# ESP32-C6-WROOM_Breakout.net
KiCad netlist of a schematic drawn in EAGLE
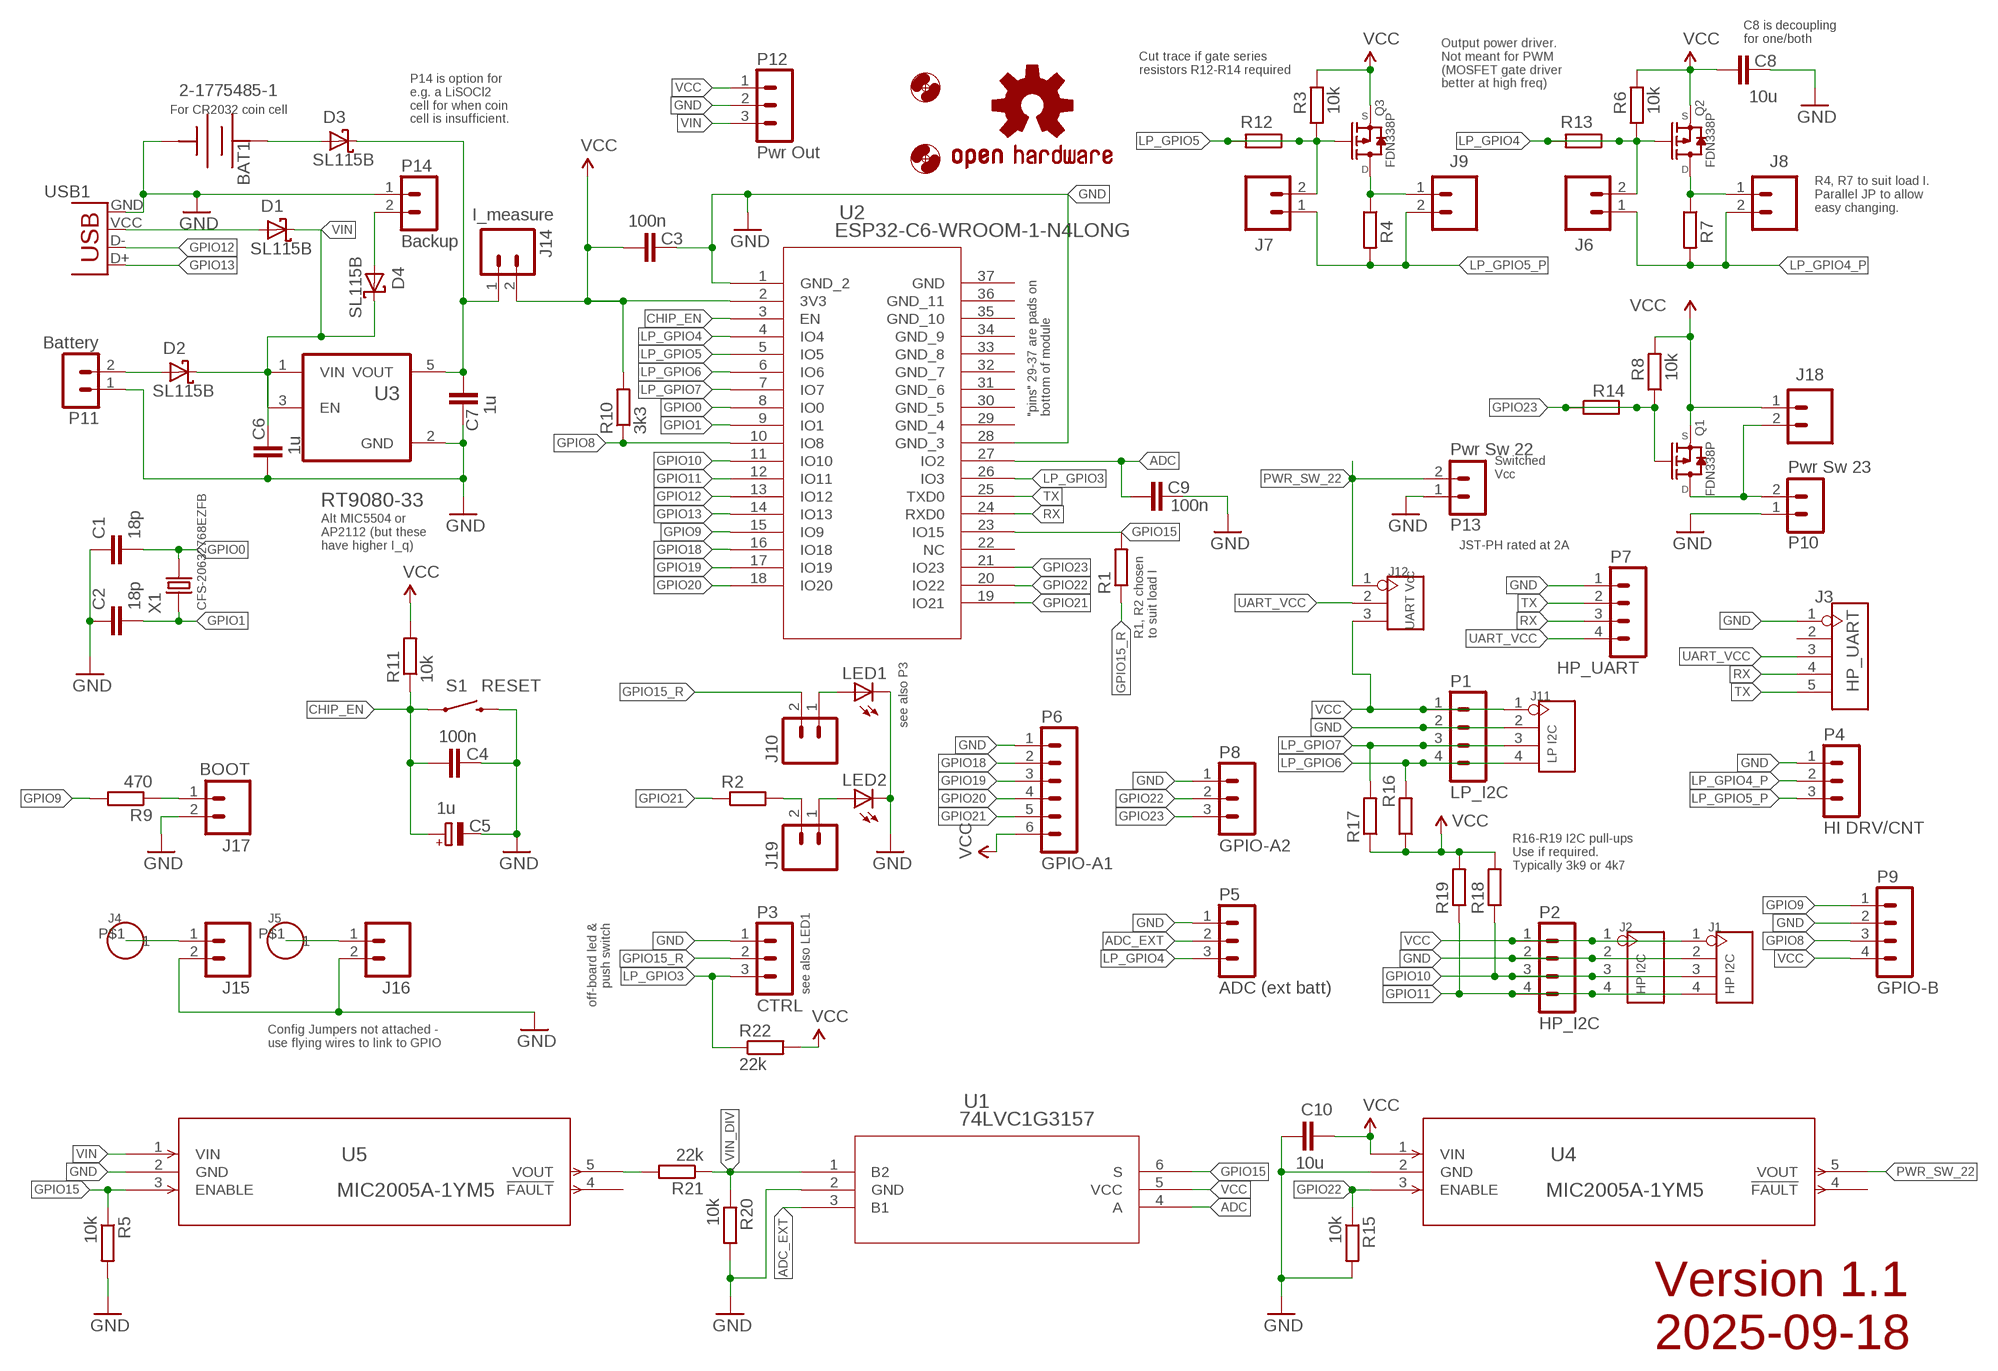
[diagram p0: schematic, sheet 1]

(export (version "E")
  (design (tool "Eeschema 10.0.6"))
  (components
    (comp (ref "BAT1")
      (value "2-1775485-1")
      (footprint "eagle-import:COIN_2-1775485-1_TEC")
      (libsource (lib "eagle-import") (part "COIN-CELL"))
    )
    (comp (ref "C1")
      (value "18p")
      (footprint "eagle-import:1206")
      (libsource (lib "eagle-import") (part "C-EU1206"))
    )
    (comp (ref "C2")
      (value "18p")
      (footprint "eagle-import:1206")
      (libsource (lib "eagle-import") (part "C-EU1206"))
    )
    (comp (ref "C3")
      (value "100n")
      (footprint "eagle-import:1206")
      (libsource (lib "eagle-import") (part "C-EU1206"))
    )
    (comp (ref "C4")
      (value "100n")
      (footprint "eagle-import:1206")
      (libsource (lib "eagle-import") (part "C-EU1206"))
    )
    (comp (ref "C5")
      (value "1u")
      (footprint "eagle-import:E2,5-5")
      (libsource (lib "eagle-import") (part "CPOL-EUE2.5-510UF"))
    )
    (comp (ref "C6")
      (value "1u")
      (footprint "eagle-import:1206")
      (libsource (lib "eagle-import") (part "C-EU1206"))
    )
    (comp (ref "C7")
      (value "1u")
      (footprint "eagle-import:1206")
      (libsource (lib "eagle-import") (part "C-EU1206"))
    )
    (comp (ref "C8")
      (value "10u")
      (footprint "eagle-import:1206")
      (libsource (lib "eagle-import") (part "C-EU1206"))
    )
    (comp (ref "C9")
      (value "100n")
      (footprint "eagle-import:1206")
      (libsource (lib "eagle-import") (part "C-EU1206"))
    )
    (comp (ref "C10")
      (value "10u")
      (footprint "eagle-import:1206")
      (libsource (lib "eagle-import") (part "C-EU1206"))
    )
    (comp (ref "D1")
      (value "SL115B")
      (footprint "eagle-import:DO-214AA")
      (libsource (lib "eagle-import") (part "DIODE-SCHOTTKY"))
    )
    (comp (ref "D2")
      (value "SL115B")
      (footprint "eagle-import:DO-214AA")
      (libsource (lib "eagle-import") (part "DIODE-SCHOTTKY"))
    )
    (comp (ref "D3")
      (value "SL115B")
      (footprint "eagle-import:DO-214AA")
      (libsource (lib "eagle-import") (part "DIODE-SCHOTTKY"))
    )
    (comp (ref "D4")
      (value "SL115B")
      (footprint "eagle-import:DO-214AA")
      (libsource (lib "eagle-import") (part "DIODE-SCHOTTKY"))
    )
    (comp (ref "H1")
      (value "MOUNT-HOLE2.8")
      (footprint "eagle-import:2,8")
      (libsource (lib "eagle-import") (part "MOUNT-HOLE2.8"))
    )
    (comp (ref "H2")
      (value "MOUNT-HOLE2.8")
      (footprint "eagle-import:2,8")
      (libsource (lib "eagle-import") (part "MOUNT-HOLE2.8"))
    )
    (comp (ref "J1")
      (value "HP I2C")
      (footprint "eagle-import:4P-2.54-80_40MIL")
      (libsource (lib "eagle-import") (part "HEADER-4P-80/40MIL"))
    )
    (comp (ref "J2")
      (value "HP I2C")
      (footprint "eagle-import:4P-2.54-80_40MIL")
      (libsource (lib "eagle-import") (part "HEADER-4P-80/40MIL"))
    )
    (comp (ref "J3")
      (value "HP_UART")
      (footprint "eagle-import:5P-2.54")
      (libsource (lib "eagle-import") (part "HEADER-5P-2.54"))
    )
    (comp (ref "J4")
      (value "HEADER-1P-35")
      (footprint "eagle-import:1P-65_35MIL")
      (libsource (lib "eagle-import") (part "HEADER-1P-35"))
    )
    (comp (ref "J5")
      (value "HEADER-1P-35")
      (footprint "eagle-import:1P-65_35MIL")
      (libsource (lib "eagle-import") (part "HEADER-1P-35"))
    )
    (comp (ref "J6")
      (value "HEADER-1X2PPTH")
      (footprint "eagle-import:1X02")
      (libsource (lib "eagle-import") (part "HEADER-1X2PPTH"))
    )
    (comp (ref "J7")
      (value "HEADER-1X2PPTH")
      (footprint "eagle-import:1X02")
      (libsource (lib "eagle-import") (part "HEADER-1X2PPTH"))
    )
    (comp (ref "J8")
      (value "HEADER-1X2PPTH")
      (footprint "eagle-import:1X02")
      (libsource (lib "eagle-import") (part "HEADER-1X2PPTH"))
    )
    (comp (ref "J9")
      (value "HEADER-1X2PPTH")
      (footprint "eagle-import:1X02")
      (libsource (lib "eagle-import") (part "HEADER-1X2PPTH"))
    )
    (comp (ref "J10")
      (value "HEADER-1X2PPTH")
      (footprint "eagle-import:1X02")
      (libsource (lib "eagle-import") (part "HEADER-1X2PPTH"))
    )
    (comp (ref "J11")
      (value "LP I2C")
      (footprint "eagle-import:4P-2.54-80_40MIL")
      (libsource (lib "eagle-import") (part "HEADER-4P-80/40MIL"))
    )
    (comp (ref "J12")
      (value "UART Vcc")
      (footprint "eagle-import:3P-2.54")
      (libsource (lib "eagle-import") (part "HEADER-3P-2.54"))
    )
    (comp (ref "J14")
      (value "I_measure")
      (footprint "eagle-import:1X02")
      (libsource (lib "eagle-import") (part "HEADER-1X2PPTH"))
    )
    (comp (ref "J15")
      (value "HEADER-1X2PPTH")
      (footprint "eagle-import:1X02")
      (libsource (lib "eagle-import") (part "HEADER-1X2PPTH"))
    )
    (comp (ref "J16")
      (value "HEADER-1X2PPTH")
      (footprint "eagle-import:1X02")
      (libsource (lib "eagle-import") (part "HEADER-1X2PPTH"))
    )
    (comp (ref "J17")
      (value "BOOT")
      (footprint "eagle-import:1X02")
      (libsource (lib "eagle-import") (part "HEADER-1X2PPTH"))
    )
    (comp (ref "J18")
      (value "HEADER-1X2PPTH")
      (footprint "eagle-import:1X02")
      (libsource (lib "eagle-import") (part "HEADER-1X2PPTH"))
    )
    (comp (ref "J19")
      (value "HEADER-1X2PPTH")
      (footprint "eagle-import:1X02")
      (libsource (lib "eagle-import") (part "HEADER-1X2PPTH"))
    )
    (comp (ref "LED1")
      (value "LED1206")
      (footprint "eagle-import:LED-1206")
      (libsource (lib "eagle-import") (part "LED1206"))
    )
    (comp (ref "LED2")
      (value "LED1206")
      (footprint "eagle-import:LED-1206")
      (libsource (lib "eagle-import") (part "LED1206"))
    )
    (comp (ref "LOGO1")
      (value "OSHW-LOGOL")
      (footprint "eagle-import:OSHW-LOGO-L")
      (libsource (lib "eagle-import") (part "OSHW-LOGOL"))
    )
    (comp (ref "P1")
      (value "LP_I2C")
      (footprint "eagle-import:B4B-EH-A")
      (libsource (lib "eagle-import") (part "B4B-EH-A"))
    )
    (comp (ref "P2")
      (value "HP_I2C")
      (footprint "eagle-import:B4B-EH-A")
      (libsource (lib "eagle-import") (part "B4B-EH-A"))
    )
    (comp (ref "P3")
      (value "CTRL")
      (footprint "eagle-import:B3B-EH-A")
      (libsource (lib "eagle-import") (part "B3B-EH-A"))
    )
    (comp (ref "P4")
      (value "HI DRV/CNT")
      (footprint "eagle-import:B3B-EH-A")
      (libsource (lib "eagle-import") (part "B3B-EH-A"))
    )
    (comp (ref "P5")
      (value "ADC (ext batt)")
      (footprint "eagle-import:B3B-EH-A")
      (libsource (lib "eagle-import") (part "B3B-EH-A"))
    )
    (comp (ref "P6")
      (value "GPIO-A1")
      (footprint "eagle-import:B6B-EH-A")
      (libsource (lib "eagle-import") (part "B6B-EH-A"))
    )
    (comp (ref "P7")
      (value "HP_UART")
      (footprint "eagle-import:B4B-EH-A")
      (libsource (lib "eagle-import") (part "B4B-EH-A"))
    )
    (comp (ref "P8")
      (value "GPIO-A2")
      (footprint "eagle-import:B3B-EH-A")
      (libsource (lib "eagle-import") (part "B3B-EH-A"))
    )
    (comp (ref "P9")
      (value "GPIO-B")
      (footprint "eagle-import:B4B-EH-A")
      (libsource (lib "eagle-import") (part "B4B-EH-A"))
    )
    (comp (ref "P10")
      (value "Pwr Sw 23")
      (footprint "eagle-import:B2B-PH-K")
      (libsource (lib "eagle-import") (part "B2B-PH-K"))
    )
    (comp (ref "P11")
      (value "Battery")
      (footprint "eagle-import:B2B-PH-K")
      (libsource (lib "eagle-import") (part "B2B-PH-K"))
    )
    (comp (ref "P12")
      (value "Pwr Out")
      (footprint "eagle-import:B3B-PH-K")
      (libsource (lib "eagle-import") (part "B3B-PH-K"))
    )
    (comp (ref "P13")
      (value "Pwr Sw 22")
      (footprint "eagle-import:B2B-PH-K")
      (libsource (lib "eagle-import") (part "B2B-PH-K"))
    )
    (comp (ref "P14")
      (value "Backup")
      (footprint "eagle-import:B2B-PH-K")
      (libsource (lib "eagle-import") (part "B2B-PH-K"))
    )
    (comp (ref "Q1")
      (value "FDN338P")
      (footprint "eagle-import:SOT23_LONG")
      (libsource (lib "eagle-import") (part "FDN338P_PMOSSOT23_LONG"))
    )
    (comp (ref "Q2")
      (value "FDN338P")
      (footprint "eagle-import:SOT23_LONG")
      (libsource (lib "eagle-import") (part "FDN338P_PMOSSOT23_LONG"))
    )
    (comp (ref "Q3")
      (value "FDN338P")
      (footprint "eagle-import:SOT23_LONG")
      (libsource (lib "eagle-import") (part "FDN338P_PMOSSOT23_LONG"))
    )
    (comp (ref "R1")
      (value "R-EU_")
      (footprint "eagle-import:1206")
      (libsource (lib "eagle-import") (part "R-EU_"))
    )
    (comp (ref "R2")
      (value "R-EU_")
      (footprint "eagle-import:1206")
      (libsource (lib "eagle-import") (part "R-EU_"))
    )
    (comp (ref "R3")
      (value "10k")
      (footprint "eagle-import:1206")
      (libsource (lib "eagle-import") (part "R-EU_"))
    )
    (comp (ref "R4")
      (value "R-EU_")
      (footprint "eagle-import:1206")
      (libsource (lib "eagle-import") (part "R-EU_"))
    )
    (comp (ref "R5")
      (value "10k")
      (footprint "eagle-import:1206")
      (libsource (lib "eagle-import") (part "R-EU_"))
    )
    (comp (ref "R6")
      (value "10k")
      (footprint "eagle-import:1206")
      (libsource (lib "eagle-import") (part "R-EU_"))
    )
    (comp (ref "R7")
      (value "R-EU_")
      (footprint "eagle-import:1206")
      (libsource (lib "eagle-import") (part "R-EU_"))
    )
    (comp (ref "R8")
      (value "10k")
      (footprint "eagle-import:1206")
      (libsource (lib "eagle-import") (part "R-EU_"))
    )
    (comp (ref "R9")
      (value "470")
      (footprint "eagle-import:1206")
      (libsource (lib "eagle-import") (part "R-EU_"))
    )
    (comp (ref "R10")
      (value "3k3")
      (footprint "eagle-import:1206")
      (libsource (lib "eagle-import") (part "R-EU_"))
    )
    (comp (ref "R11")
      (value "10k")
      (footprint "eagle-import:1206")
      (libsource (lib "eagle-import") (part "R-EU_"))
    )
    (comp (ref "R12")
      (value "R-EU_")
      (footprint "eagle-import:1206")
      (libsource (lib "eagle-import") (part "R-EU_"))
    )
    (comp (ref "R13")
      (value "R-EU_")
      (footprint "eagle-import:1206")
      (libsource (lib "eagle-import") (part "R-EU_"))
    )
    (comp (ref "R14")
      (value "R-EU_")
      (footprint "eagle-import:1206")
      (libsource (lib "eagle-import") (part "R-EU_"))
    )
    (comp (ref "R15")
      (value "10k")
      (footprint "eagle-import:1206")
      (libsource (lib "eagle-import") (part "R-EU_"))
    )
    (comp (ref "R16")
      (value "4k7")
      (footprint "eagle-import:1206")
      (libsource (lib "eagle-import") (part "R-EU_"))
    )
    (comp (ref "R17")
      (value "4k7")
      (footprint "eagle-import:1206")
      (libsource (lib "eagle-import") (part "R-EU_"))
    )
    (comp (ref "R18")
      (value "4k7")
      (footprint "eagle-import:1206")
      (libsource (lib "eagle-import") (part "R-EU_"))
    )
    (comp (ref "R19")
      (value "4k7")
      (footprint "eagle-import:1206")
      (libsource (lib "eagle-import") (part "R-EU_"))
    )
    (comp (ref "R20")
      (value "10k")
      (footprint "eagle-import:1206")
      (libsource (lib "eagle-import") (part "R-EU_"))
    )
    (comp (ref "R21")
      (value "22k")
      (footprint "eagle-import:1206")
      (libsource (lib "eagle-import") (part "R-EU_"))
    )
    (comp (ref "R22")
      (value "22k")
      (footprint "eagle-import:1206")
      (libsource (lib "eagle-import") (part "R-EU_"))
    )
    (comp (ref "S1")
      (value "RESET")
      (footprint "eagle-import:TACTILE-PTH")
      (libsource (lib "eagle-import") (part "SWITCH-MOMENTARY-2PTH"))
    )
    (comp (ref "U1")
      (value "74LVC1G3157")
      (footprint "eagle-import:DBV6")
      (fields
        (field (name "MANUFACTURER_PART_NUMBER") "SN74LVC1G3157DBVR")
        (field (name "COPYRIGHT") "Copyright (C) 2025 Ultra Librarian. All rights reserved.")
      )
      (libsource (lib "eagle-import") (part "SN74LVC1G3157DBVR"))
    )
    (comp (ref "U2")
      (value "ESP32-C6-WROOM-1-N4LONG")
      (footprint "eagle-import:MOD28_ESP32-C6-WROOM-1_LONG")
      (libsource (lib "eagle-import") (part "ESP32-C6-WROOM-1-N4LONG"))
    )
    (comp (ref "U3")
      (value "RT9080-33")
      (footprint "eagle-import:SOT95-LONGPADS")
      (libsource (lib "eagle-import") (part "AP2112K-3.3TRG1LONG_PADS"))
    )
    (comp (ref "U4")
      (value "MIC2005A-1YM5")
      (footprint "eagle-import:SOT-23-5_M5_MCH-M")
      (fields
        (field (name "MANUFACTURER_PART_NUMBER") "MIC2005A-1YM5-TR")
        (field (name "COPYRIGHT") "Copyright (C) 2025 Ultra Librarian. All rights reserved.")
      )
      (libsource (lib "eagle-import") (part "MIC2005A-1YM5-TRSOT-23-5_M5_MCH-M"))
    )
    (comp (ref "U5")
      (value "MIC2005A-1YM5")
      (footprint "eagle-import:SOT-23-5_M5_MCH-M")
      (fields
        (field (name "MANUFACTURER_PART_NUMBER") "MIC2005A-1YM5-TR")
        (field (name "COPYRIGHT") "Copyright (C) 2025 Ultra Librarian. All rights reserved.")
      )
      (libsource (lib "eagle-import") (part "MIC2005A-1YM5-TRSOT-23-5_M5_MCH-M"))
    )
    (comp (ref "USB1")
      (value "USB-FCI_SMD_LONG***")
      (footprint "eagle-import:FCI_USB_B_SMD_LONG")
      (libsource (lib "eagle-import") (part "USB-FCI_SMD_LONG"))
    )
    (comp (ref "X1")
      (value "CFS-20632768EZFB")
      (footprint "eagle-import:TC26H")
      (libsource (lib "eagle-import") (part "CRYSTAL-TC26H"))
    )
  )
  (nets
    (net (code "1") (name "ADC") (class "Default")
      (node (ref "C9") (pin "1") (pinfunction "1_1") (pintype "passive"))
      (node (ref "U1") (pin "4") (pinfunction "A_4") (pintype "input"))
      (node (ref "U2") (pin "27") (pinfunction "IO2_27") (pintype "bidirectional"))
    )
    (net (code "2") (name "ADC_EXT") (class "Default")
      (node (ref "P5") (pin "2") (pinfunction "2_2") (pintype "passive"))
      (node (ref "U1") (pin "3") (pinfunction "B1_3") (pintype "input"))
    )
    (net (code "3") (name "CHIP_EN") (class "Default")
      (node (ref "C4") (pin "2") (pinfunction "2_2") (pintype "passive"))
      (node (ref "C5") (pin "+") (pinfunction "+_+") (pintype "passive"))
      (node (ref "R11") (pin "1") (pinfunction "1_1") (pintype "passive"))
      (node (ref "S1") (pin "1") (pinfunction "1_1") (pintype "passive"))
      (node (ref "U2") (pin "3") (pinfunction "EN_3") (pintype "input"))
    )
    (net (code "4") (name "GND") (class "Default")
      (node (ref "BAT1") (pin "2") (pinfunction "NEG_2") (pintype "bidirectional"))
      (node (ref "C1") (pin "1") (pinfunction "1_1") (pintype "passive"))
      (node (ref "C10") (pin "1") (pinfunction "1_1") (pintype "passive"))
      (node (ref "C2") (pin "1") (pinfunction "1_1") (pintype "passive"))
      (node (ref "C3") (pin "2") (pinfunction "2_2") (pintype "passive"))
      (node (ref "C4") (pin "1") (pinfunction "1_1") (pintype "passive"))
      (node (ref "C5") (pin "-") (pinfunction "-_-") (pintype "passive"))
      (node (ref "C6") (pin "2") (pinfunction "2_2") (pintype "passive"))
      (node (ref "C7") (pin "2") (pinfunction "2_2") (pintype "passive"))
      (node (ref "C8") (pin "2") (pinfunction "2_2") (pintype "passive"))
      (node (ref "C9") (pin "2") (pinfunction "2_2") (pintype "passive"))
      (node (ref "J1") (pin "2") (pinfunction "P$2_2") (pintype "bidirectional"))
      (node (ref "J11") (pin "2") (pinfunction "P$2_2") (pintype "bidirectional"))
      (node (ref "J15") (pin "2") (pinfunction "2_2") (pintype "passive"))
      (node (ref "J16") (pin "2") (pinfunction "2_2") (pintype "passive"))
      (node (ref "J17") (pin "2") (pinfunction "2_2") (pintype "passive"))
      (node (ref "J2") (pin "2") (pinfunction "P$2_2") (pintype "bidirectional"))
      (node (ref "J3") (pin "1") (pinfunction "1_1") (pintype "bidirectional"))
      (node (ref "LED1") (pin "C") (pinfunction "C_C") (pintype "passive"))
      (node (ref "LED2") (pin "C") (pinfunction "C_C") (pintype "passive"))
      (node (ref "P1") (pin "2") (pinfunction "2_2") (pintype "passive"))
      (node (ref "P10") (pin "1") (pinfunction "1_1") (pintype "passive"))
      (node (ref "P11") (pin "1") (pinfunction "1_1") (pintype "passive"))
      (node (ref "P12") (pin "2") (pinfunction "2_2") (pintype "passive"))
      (node (ref "P13") (pin "1") (pinfunction "1_1") (pintype "passive"))
      (node (ref "P14") (pin "1") (pinfunction "1_1") (pintype "passive"))
      (node (ref "P2") (pin "2") (pinfunction "2_2") (pintype "passive"))
      (node (ref "P3") (pin "1") (pinfunction "1_1") (pintype "passive"))
      (node (ref "P4") (pin "1") (pinfunction "1_1") (pintype "passive"))
      (node (ref "P5") (pin "1") (pinfunction "1_1") (pintype "passive"))
      (node (ref "P6") (pin "1") (pinfunction "1_1") (pintype "passive"))
      (node (ref "P7") (pin "1") (pinfunction "1_1") (pintype "passive"))
      (node (ref "P8") (pin "1") (pinfunction "1_1") (pintype "passive"))
      (node (ref "P9") (pin "2") (pinfunction "2_2") (pintype "passive"))
      (node (ref "R15") (pin "2") (pinfunction "2_2") (pintype "passive"))
      (node (ref "R20") (pin "2") (pinfunction "2_2") (pintype "passive"))
      (node (ref "R5") (pin "2") (pinfunction "2_2") (pintype "passive"))
      (node (ref "S1") (pin "3") (pinfunction "2_3") (pintype "passive"))
      (node (ref "U1") (pin "2") (pinfunction "GND_2") (pintype "power_in"))
      (node (ref "U2") (pin "1") (pinfunction "GND_2_1") (pintype "passive"))
      (node (ref "U2") (pin "28") (pinfunction "GND_3_28") (pintype "passive"))
      (node (ref "U3") (pin "2") (pinfunction "GND_2") (pintype "power_in"))
      (node (ref "U4") (pin "2") (pinfunction "GND_2") (pintype "power_in"))
      (node (ref "U5") (pin "2") (pinfunction "GND_2") (pintype "power_in"))
      (node (ref "USB1") (pin "GND") (pinfunction "GND_GND") (pintype "bidirectional"))
    )
    (net (code "5") (name "GPIO0") (class "Default")
      (node (ref "C1") (pin "2") (pinfunction "2_2") (pintype "passive"))
      (node (ref "U2") (pin "8") (pinfunction "IO0_8") (pintype "bidirectional"))
      (node (ref "X1") (pin "2") (pinfunction "2_2") (pintype "passive"))
    )
    (net (code "6") (name "GPIO1") (class "Default")
      (node (ref "C2") (pin "2") (pinfunction "2_2") (pintype "passive"))
      (node (ref "U2") (pin "9") (pinfunction "IO1_9") (pintype "bidirectional"))
      (node (ref "X1") (pin "1") (pinfunction "1_1") (pintype "passive"))
    )
    (net (code "7") (name "GPIO8") (class "Default")
      (node (ref "P9") (pin "3") (pinfunction "3_3") (pintype "passive"))
      (node (ref "R10") (pin "1") (pinfunction "1_1") (pintype "passive"))
      (node (ref "U2") (pin "10") (pinfunction "IO8_10") (pintype "bidirectional"))
    )
    (net (code "8") (name "GPIO9") (class "Default")
      (node (ref "P9") (pin "1") (pinfunction "1_1") (pintype "passive"))
      (node (ref "R9") (pin "2") (pinfunction "2_2") (pintype "passive"))
      (node (ref "U2") (pin "15") (pinfunction "IO9_15") (pintype "bidirectional"))
    )
    (net (code "9") (name "GPIO10") (class "Default")
      (node (ref "J1") (pin "3") (pinfunction "P$3_3") (pintype "bidirectional"))
      (node (ref "J2") (pin "3") (pinfunction "P$3_3") (pintype "bidirectional"))
      (node (ref "P2") (pin "3") (pinfunction "3_3") (pintype "passive"))
      (node (ref "R18") (pin "1") (pinfunction "1_1") (pintype "passive"))
      (node (ref "U2") (pin "11") (pinfunction "IO10_11") (pintype "bidirectional"))
    )
    (net (code "10") (name "GPIO11") (class "Default")
      (node (ref "J1") (pin "4") (pinfunction "P$4_4") (pintype "bidirectional"))
      (node (ref "J2") (pin "4") (pinfunction "P$4_4") (pintype "bidirectional"))
      (node (ref "P2") (pin "4") (pinfunction "4_4") (pintype "passive"))
      (node (ref "R19") (pin "1") (pinfunction "1_1") (pintype "passive"))
      (node (ref "U2") (pin "12") (pinfunction "IO11_12") (pintype "bidirectional"))
    )
    (net (code "11") (name "GPIO12") (class "Default")
      (node (ref "U2") (pin "13") (pinfunction "IO12_13") (pintype "bidirectional"))
      (node (ref "USB1") (pin "D-") (pinfunction "D-_D-") (pintype "bidirectional"))
    )
    (net (code "12") (name "GPIO13") (class "Default")
      (node (ref "U2") (pin "14") (pinfunction "IO13_14") (pintype "bidirectional"))
      (node (ref "USB1") (pin "D+") (pinfunction "D+_D+") (pintype "bidirectional"))
    )
    (net (code "13") (name "GPIO15") (class "Default")
      (node (ref "R1") (pin "2") (pinfunction "2_2") (pintype "passive"))
      (node (ref "R5") (pin "1") (pinfunction "1_1") (pintype "passive"))
      (node (ref "U1") (pin "6") (pinfunction "S_6") (pintype "input"))
      (node (ref "U2") (pin "23") (pinfunction "IO15_23") (pintype "bidirectional"))
      (node (ref "U5") (pin "3") (pinfunction "ENABLE_3") (pintype "input"))
    )
    (net (code "14") (name "GPIO15_R") (class "Default")
      (node (ref "J10") (pin "2") (pinfunction "2_2") (pintype "passive"))
      (node (ref "P3") (pin "2") (pinfunction "2_2") (pintype "passive"))
      (node (ref "R1") (pin "1") (pinfunction "1_1") (pintype "passive"))
    )
    (net (code "15") (name "GPIO18") (class "Default")
      (node (ref "P6") (pin "2") (pinfunction "2_2") (pintype "passive"))
      (node (ref "U2") (pin "16") (pinfunction "IO18_16") (pintype "bidirectional"))
    )
    (net (code "16") (name "GPIO19") (class "Default")
      (node (ref "P6") (pin "3") (pinfunction "3_3") (pintype "passive"))
      (node (ref "U2") (pin "17") (pinfunction "IO19_17") (pintype "bidirectional"))
    )
    (net (code "17") (name "GPIO20") (class "Default")
      (node (ref "P6") (pin "4") (pinfunction "4_4") (pintype "passive"))
      (node (ref "U2") (pin "18") (pinfunction "IO20_18") (pintype "bidirectional"))
    )
    (net (code "18") (name "GPIO21") (class "Default")
      (node (ref "P6") (pin "5") (pinfunction "5_5") (pintype "passive"))
      (node (ref "R2") (pin "1") (pinfunction "1_1") (pintype "passive"))
      (node (ref "U2") (pin "19") (pinfunction "IO21_19") (pintype "bidirectional"))
    )
    (net (code "19") (name "GPIO22") (class "Default")
      (node (ref "P8") (pin "2") (pinfunction "2_2") (pintype "passive"))
      (node (ref "R15") (pin "1") (pinfunction "1_1") (pintype "passive"))
      (node (ref "U2") (pin "20") (pinfunction "IO22_20") (pintype "bidirectional"))
      (node (ref "U4") (pin "3") (pinfunction "ENABLE_3") (pintype "input"))
    )
    (net (code "20") (name "GPIO23") (class "Default")
      (node (ref "P8") (pin "3") (pinfunction "3_3") (pintype "passive"))
      (node (ref "Q1") (pin "1") (pinfunction "G_1") (pintype "passive"))
      (node (ref "R14") (pin "1") (pinfunction "1_1") (pintype "passive"))
      (node (ref "R14") (pin "2") (pinfunction "2_2") (pintype "passive"))
      (node (ref "R8") (pin "1") (pinfunction "1_1") (pintype "passive"))
      (node (ref "U2") (pin "21") (pinfunction "IO23_21") (pintype "bidirectional"))
    )
    (net (code "21") (name "LP_GPIO3") (class "Default")
      (node (ref "P3") (pin "3") (pinfunction "3_3") (pintype "passive"))
      (node (ref "R22") (pin "1") (pinfunction "1_1") (pintype "passive"))
      (node (ref "U2") (pin "26") (pinfunction "IO3_26") (pintype "bidirectional"))
    )
    (net (code "22") (name "LP_GPIO4") (class "Default")
      (node (ref "J6") (pin "2") (pinfunction "2_2") (pintype "passive"))
      (node (ref "P5") (pin "3") (pinfunction "3_3") (pintype "passive"))
      (node (ref "Q2") (pin "1") (pinfunction "G_1") (pintype "passive"))
      (node (ref "R13") (pin "1") (pinfunction "1_1") (pintype "passive"))
      (node (ref "R13") (pin "2") (pinfunction "2_2") (pintype "passive"))
      (node (ref "R6") (pin "1") (pinfunction "1_1") (pintype "passive"))
      (node (ref "U2") (pin "4") (pinfunction "IO4_4") (pintype "bidirectional"))
    )
    (net (code "23") (name "LP_GPIO4_P") (class "Default")
      (node (ref "J6") (pin "1") (pinfunction "1_1") (pintype "passive"))
      (node (ref "J8") (pin "2") (pinfunction "2_2") (pintype "passive"))
      (node (ref "P4") (pin "2") (pinfunction "2_2") (pintype "passive"))
      (node (ref "R7") (pin "2") (pinfunction "2_2") (pintype "passive"))
    )
    (net (code "24") (name "LP_GPIO5") (class "Default")
      (node (ref "J7") (pin "2") (pinfunction "2_2") (pintype "passive"))
      (node (ref "Q3") (pin "1") (pinfunction "G_1") (pintype "passive"))
      (node (ref "R12") (pin "1") (pinfunction "1_1") (pintype "passive"))
      (node (ref "R12") (pin "2") (pinfunction "2_2") (pintype "passive"))
      (node (ref "R3") (pin "1") (pinfunction "1_1") (pintype "passive"))
      (node (ref "U2") (pin "5") (pinfunction "IO5_5") (pintype "bidirectional"))
    )
    (net (code "25") (name "LP_GPIO5_P") (class "Default")
      (node (ref "J7") (pin "1") (pinfunction "1_1") (pintype "passive"))
      (node (ref "J9") (pin "2") (pinfunction "2_2") (pintype "passive"))
      (node (ref "P4") (pin "3") (pinfunction "3_3") (pintype "passive"))
      (node (ref "R4") (pin "2") (pinfunction "2_2") (pintype "passive"))
    )
    (net (code "26") (name "LP_GPIO6") (class "Default")
      (node (ref "J11") (pin "4") (pinfunction "P$4_4") (pintype "bidirectional"))
      (node (ref "P1") (pin "4") (pinfunction "4_4") (pintype "passive"))
      (node (ref "R16") (pin "2") (pinfunction "2_2") (pintype "passive"))
      (node (ref "U2") (pin "6") (pinfunction "IO6_6") (pintype "bidirectional"))
    )
    (net (code "27") (name "LP_GPIO7") (class "Default")
      (node (ref "J11") (pin "3") (pinfunction "P$3_3") (pintype "bidirectional"))
      (node (ref "P1") (pin "3") (pinfunction "3_3") (pintype "passive"))
      (node (ref "R17") (pin "2") (pinfunction "2_2") (pintype "passive"))
      (node (ref "U2") (pin "7") (pinfunction "IO7_7") (pintype "bidirectional"))
    )
    (net (code "28") (name "Net-(BAT1-POS-Pad1)") (class "Default")
      (node (ref "BAT1") (pin "1") (pinfunction "POS_1") (pintype "bidirectional"))
      (node (ref "BAT1") (pin "3") (pinfunction "POS_3") (pintype "bidirectional"))
      (node (ref "D3") (pin "A") (pinfunction "A_A") (pintype "passive"))
    )
    (net (code "29") (name "Net-(D2-PadA)") (class "Default")
      (node (ref "D2") (pin "A") (pinfunction "A_A") (pintype "passive"))
      (node (ref "P11") (pin "2") (pinfunction "2_2") (pintype "passive"))
    )
    (net (code "30") (name "Net-(D4-PadA)") (class "Default")
      (node (ref "D4") (pin "A") (pinfunction "A_A") (pintype "passive"))
      (node (ref "P14") (pin "2") (pinfunction "2_2") (pintype "passive"))
    )
    (net (code "31") (name "Net-(J4-1)") (class "Default")
      (node (ref "J15") (pin "1") (pinfunction "1_1") (pintype "passive"))
      (node (ref "J4") (pin "P$1") (pinfunction "1_P$1") (pintype "bidirectional"))
    )
    (net (code "32") (name "Net-(J5-1)") (class "Default")
      (node (ref "J16") (pin "1") (pinfunction "1_1") (pintype "passive"))
      (node (ref "J5") (pin "P$1") (pinfunction "1_P$1") (pintype "bidirectional"))
    )
    (net (code "33") (name "Net-(J10-Pad1)") (class "Default")
      (node (ref "J10") (pin "1") (pinfunction "1_1") (pintype "passive"))
      (node (ref "LED1") (pin "A") (pinfunction "A_A") (pintype "passive"))
    )
    (net (code "34") (name "Net-(J17-Pad1)") (class "Default")
      (node (ref "J17") (pin "1") (pinfunction "1_1") (pintype "passive"))
      (node (ref "R9") (pin "1") (pinfunction "1_1") (pintype "passive"))
    )
    (net (code "35") (name "Net-(J19-Pad1)") (class "Default")
      (node (ref "J19") (pin "1") (pinfunction "1_1") (pintype "passive"))
      (node (ref "LED2") (pin "A") (pinfunction "A_A") (pintype "passive"))
    )
    (net (code "36") (name "Net-(J19-Pad2)") (class "Default")
      (node (ref "J19") (pin "2") (pinfunction "2_2") (pintype "passive"))
      (node (ref "R2") (pin "2") (pinfunction "2_2") (pintype "passive"))
    )
    (net (code "37") (name "Net-(Q1-D)") (class "Default")
      (node (ref "J18") (pin "2") (pinfunction "2_2") (pintype "passive"))
      (node (ref "P10") (pin "2") (pinfunction "2_2") (pintype "passive"))
      (node (ref "Q1") (pin "3") (pinfunction "D_3") (pintype "passive"))
    )
    (net (code "38") (name "Net-(Q2-D)") (class "Default")
      (node (ref "J8") (pin "1") (pinfunction "1_1") (pintype "passive"))
      (node (ref "Q2") (pin "3") (pinfunction "D_3") (pintype "passive"))
      (node (ref "R7") (pin "1") (pinfunction "1_1") (pintype "passive"))
    )
    (net (code "39") (name "Net-(Q3-D)") (class "Default")
      (node (ref "J9") (pin "1") (pinfunction "1_1") (pintype "passive"))
      (node (ref "Q3") (pin "3") (pinfunction "D_3") (pintype "passive"))
      (node (ref "R4") (pin "1") (pinfunction "1_1") (pintype "passive"))
    )
    (net (code "40") (name "Net-(U3-VOUT)") (class "Default")
      (node (ref "C7") (pin "1") (pinfunction "1_1") (pintype "passive"))
      (node (ref "D3") (pin "C") (pinfunction "C_C") (pintype "passive"))
      (node (ref "J14") (pin "1") (pinfunction "1_1") (pintype "passive"))
      (node (ref "U3") (pin "5") (pinfunction "VOUT_5") (pintype "power_in"))
    )
    (net (code "41") (name "Net-(U5-VOUT)") (class "Default")
      (node (ref "R21") (pin "2") (pinfunction "2_2") (pintype "passive"))
      (node (ref "U5") (pin "5") (pinfunction "VOUT_5") (pintype "output"))
    )
    (net (code "42") (name "Net-(USB1-VBUS)") (class "Default")
      (node (ref "D1") (pin "A") (pinfunction "A_A") (pintype "passive"))
      (node (ref "USB1") (pin "VCC") (pinfunction "VBUS_VCC") (pintype "bidirectional"))
    )
    (net (code "43") (name "PWR_SW_22") (class "Default")
      (node (ref "J12") (pin "1") (pinfunction "P$1_1") (pintype "bidirectional"))
      (node (ref "P13") (pin "2") (pinfunction "2_2") (pintype "passive"))
      (node (ref "U4") (pin "5") (pinfunction "VOUT_5") (pintype "output"))
    )
    (net (code "44") (name "RX") (class "Default")
      (node (ref "J3") (pin "4") (pinfunction "4_4") (pintype "bidirectional"))
      (node (ref "P7") (pin "3") (pinfunction "3_3") (pintype "passive"))
      (node (ref "U2") (pin "24") (pinfunction "RXD0_24") (pintype "bidirectional"))
    )
    (net (code "45") (name "TX") (class "Default")
      (node (ref "J3") (pin "5") (pinfunction "5_5") (pintype "bidirectional"))
      (node (ref "P7") (pin "2") (pinfunction "2_2") (pintype "passive"))
      (node (ref "U2") (pin "25") (pinfunction "TXD0_25") (pintype "bidirectional"))
    )
    (net (code "46") (name "UART_VCC") (class "Default")
      (node (ref "J12") (pin "2") (pinfunction "P$2_2") (pintype "bidirectional"))
      (node (ref "J3") (pin "3") (pinfunction "3_3") (pintype "bidirectional"))
      (node (ref "P7") (pin "4") (pinfunction "4_4") (pintype "passive"))
    )
    (net (code "47") (name "VCC") (class "Default")
      (node (ref "C10") (pin "2") (pinfunction "2_2") (pintype "passive"))
      (node (ref "C3") (pin "1") (pinfunction "1_1") (pintype "passive"))
      (node (ref "C8") (pin "1") (pinfunction "1_1") (pintype "passive"))
      (node (ref "J1") (pin "1") (pinfunction "P$1_1") (pintype "bidirectional"))
      (node (ref "J11") (pin "1") (pinfunction "P$1_1") (pintype "bidirectional"))
      (node (ref "J12") (pin "3") (pinfunction "P$3_3") (pintype "bidirectional"))
      (node (ref "J14") (pin "2") (pinfunction "2_2") (pintype "passive"))
      (node (ref "J18") (pin "1") (pinfunction "1_1") (pintype "passive"))
      (node (ref "J2") (pin "1") (pinfunction "P$1_1") (pintype "bidirectional"))
      (node (ref "P1") (pin "1") (pinfunction "1_1") (pintype "passive"))
      (node (ref "P12") (pin "1") (pinfunction "1_1") (pintype "passive"))
      (node (ref "P2") (pin "1") (pinfunction "1_1") (pintype "passive"))
      (node (ref "P6") (pin "6") (pinfunction "6_6") (pintype "passive"))
      (node (ref "P9") (pin "4") (pinfunction "4_4") (pintype "passive"))
      (node (ref "Q1") (pin "2") (pinfunction "S_2") (pintype "passive"))
      (node (ref "Q2") (pin "2") (pinfunction "S_2") (pintype "passive"))
      (node (ref "Q3") (pin "2") (pinfunction "S_2") (pintype "passive"))
      (node (ref "R10") (pin "2") (pinfunction "2_2") (pintype "passive"))
      (node (ref "R11") (pin "2") (pinfunction "2_2") (pintype "passive"))
      (node (ref "R16") (pin "1") (pinfunction "1_1") (pintype "passive"))
      (node (ref "R17") (pin "1") (pinfunction "1_1") (pintype "passive"))
      (node (ref "R18") (pin "2") (pinfunction "2_2") (pintype "passive"))
      (node (ref "R19") (pin "2") (pinfunction "2_2") (pintype "passive"))
      (node (ref "R22") (pin "2") (pinfunction "2_2") (pintype "passive"))
      (node (ref "R3") (pin "2") (pinfunction "2_2") (pintype "passive"))
      (node (ref "R6") (pin "2") (pinfunction "2_2") (pintype "passive"))
      (node (ref "R8") (pin "2") (pinfunction "2_2") (pintype "passive"))
      (node (ref "U1") (pin "5") (pinfunction "VCC_5") (pintype "power_in"))
      (node (ref "U2") (pin "2") (pinfunction "3V3_2") (pintype "power_in"))
      (node (ref "U4") (pin "1") (pinfunction "VIN_1") (pintype "input"))
    )
    (net (code "48") (name "VIN") (class "Default")
      (node (ref "C6") (pin "1") (pinfunction "1_1") (pintype "passive"))
      (node (ref "D1") (pin "C") (pinfunction "C_C") (pintype "passive"))
      (node (ref "D2") (pin "C") (pinfunction "C_C") (pintype "passive"))
      (node (ref "D4") (pin "C") (pinfunction "C_C") (pintype "passive"))
      (node (ref "P12") (pin "3") (pinfunction "3_3") (pintype "passive"))
      (node (ref "U3") (pin "1") (pinfunction "VIN_1") (pintype "power_in"))
      (node (ref "U3") (pin "3") (pinfunction "EN_3") (pintype "input"))
      (node (ref "U5") (pin "1") (pinfunction "VIN_1") (pintype "input"))
    )
    (net (code "49") (name "VIN_DIV") (class "Default")
      (node (ref "R20") (pin "1") (pinfunction "1_1") (pintype "passive"))
      (node (ref "R21") (pin "1") (pinfunction "1_1") (pintype "passive"))
      (node (ref "U1") (pin "1") (pinfunction "B2_1") (pintype "input"))
    )
    (net (code "50") (name "unconnected-(J3-Pad2)") (class "Default")
      (node (ref "J3") (pin "2") (pinfunction "2_2") (pintype "bidirectional"))
    )
    (net (code "51") (name "unconnected-(U2-GND-Pad37)") (class "Default")
      (node (ref "U2") (pin "37") (pinfunction "GND_37") (pintype "passive"))
    )
    (net (code "52") (name "unconnected-(U2-GND_4-Pad29)") (class "Default")
      (node (ref "U2") (pin "29") (pinfunction "GND_4_29") (pintype "passive"))
    )
    (net (code "53") (name "unconnected-(U2-GND_5-Pad30)") (class "Default")
      (node (ref "U2") (pin "30") (pinfunction "GND_5_30") (pintype "passive"))
    )
    (net (code "54") (name "unconnected-(U2-GND_6-Pad31)") (class "Default")
      (node (ref "U2") (pin "31") (pinfunction "GND_6_31") (pintype "passive"))
    )
    (net (code "55") (name "unconnected-(U2-GND_7-Pad32)") (class "Default")
      (node (ref "U2") (pin "32") (pinfunction "GND_7_32") (pintype "passive"))
    )
    (net (code "56") (name "unconnected-(U2-GND_8-Pad33)") (class "Default")
      (node (ref "U2") (pin "33") (pinfunction "GND_8_33") (pintype "passive"))
    )
    (net (code "57") (name "unconnected-(U2-GND_9-Pad34)") (class "Default")
      (node (ref "U2") (pin "34") (pinfunction "GND_9_34") (pintype "passive"))
    )
    (net (code "58") (name "unconnected-(U2-GND_10-Pad35)") (class "Default")
      (node (ref "U2") (pin "35") (pinfunction "GND_10_35") (pintype "passive"))
    )
    (net (code "59") (name "unconnected-(U2-GND_11-Pad36)") (class "Default")
      (node (ref "U2") (pin "36") (pinfunction "GND_11_36") (pintype "passive"))
    )
    (net (code "60") (name "unconnected-(U2-NC-Pad22)") (class "Default")
      (node (ref "U2") (pin "22") (pinfunction "NC_22") (pintype "no_connect"))
    )
    (net (code "61") (name "unconnected-(U4-~{FAULT}-Pad4)") (class "Default")
      (node (ref "U4") (pin "4") (pinfunction "~{FAULT}_4") (pintype "output"))
    )
    (net (code "62") (name "unconnected-(U5-~{FAULT}-Pad4)") (class "Default")
      (node (ref "U5") (pin "4") (pinfunction "~{FAULT}_4") (pintype "output"))
    )
  )
)
